# master2.net
KiCad netlist of a schematic drawn in EAGLE
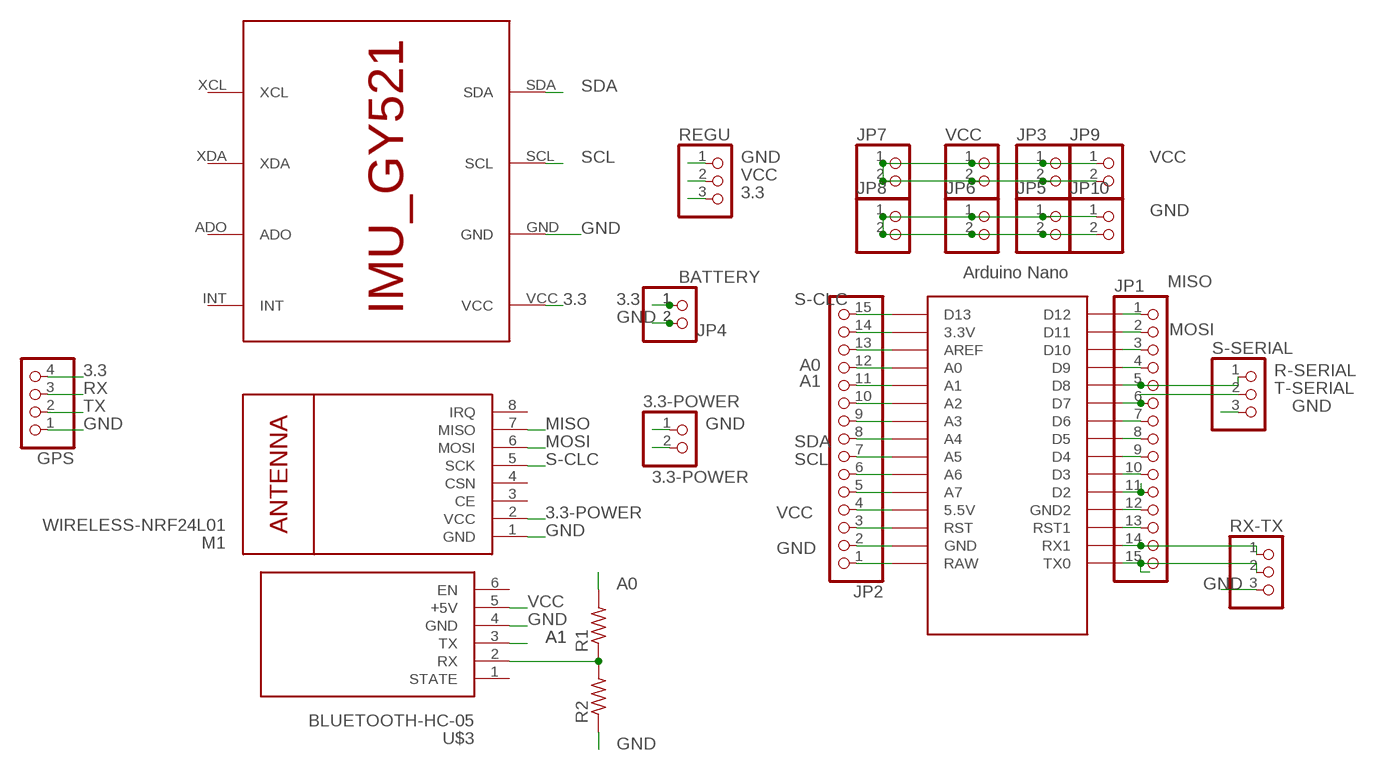
[diagram p0: schematic, sheet 1]

(export (version "E")
  (design (tool "Eeschema 10.0.6"))
  (components
    (comp (ref "3.3-POWER")
      (value "PINHD-2_DATA")
      (footprint "eagle-import:1X02_DATA")
      (libsource (lib "eagle-import") (part "PINHD-2_DATA"))
    )
    (comp (ref "BATTERY")
      (value "PINHD-2_DATA")
      (footprint "eagle-import:1X02_DATA")
      (libsource (lib "eagle-import") (part "PINHD-2_DATA"))
    )
    (comp (ref "GPS")
      (value "PINHD-1X4")
      (footprint "eagle-import:1X04")
      (libsource (lib "eagle-import") (part "PINHD-1X4"))
    )
    (comp (ref "JP1")
      (value "PINHD-1X15")
      (footprint "eagle-import:1X15")
      (libsource (lib "eagle-import") (part "PINHD-1X15"))
    )
    (comp (ref "JP2")
      (value "PINHD-1X15")
      (footprint "eagle-import:1X15")
      (libsource (lib "eagle-import") (part "PINHD-1X15"))
    )
    (comp (ref "JP3")
      (value "PINHD-1X2")
      (footprint "eagle-import:1X02")
      (libsource (lib "eagle-import") (part "PINHD-1X2"))
    )
    (comp (ref "JP4")
      (value "PINHD-2_DATA")
      (footprint "eagle-import:1X02_DATA")
      (libsource (lib "eagle-import") (part "PINHD-2_DATA"))
    )
    (comp (ref "JP5")
      (value "PINHD-1X2")
      (footprint "eagle-import:1X02")
      (libsource (lib "eagle-import") (part "PINHD-1X2"))
    )
    (comp (ref "JP6")
      (value "PINHD-1X2")
      (footprint "eagle-import:1X02")
      (libsource (lib "eagle-import") (part "PINHD-1X2"))
    )
    (comp (ref "JP7")
      (value "PINHD-1X2")
      (footprint "eagle-import:1X02")
      (libsource (lib "eagle-import") (part "PINHD-1X2"))
    )
    (comp (ref "JP8")
      (value "PINHD-1X2")
      (footprint "eagle-import:1X02")
      (libsource (lib "eagle-import") (part "PINHD-1X2"))
    )
    (comp (ref "JP9")
      (value "PINHD-1X2")
      (footprint "eagle-import:1X02")
      (libsource (lib "eagle-import") (part "PINHD-1X2"))
    )
    (comp (ref "JP10")
      (value "PINHD-1X2")
      (footprint "eagle-import:1X02")
      (libsource (lib "eagle-import") (part "PINHD-1X2"))
    )
    (comp (ref "M1")
      (value "WIRELESS-NRF24L01")
      (footprint "eagle-import:WIRELESS-NRF24L01")
      (libsource (lib "eagle-import") (part "WIRELESS-NRF24L01"))
    )
    (comp (ref "R1")
      (value "R-US_0204/2V")
      (footprint "eagle-import:0204V")
      (libsource (lib "eagle-import") (part "R-US_0204/2V"))
    )
    (comp (ref "R2")
      (value "R-US_0204/2V")
      (footprint "eagle-import:0204V")
      (libsource (lib "eagle-import") (part "R-US_0204/2V"))
    )
    (comp (ref "REGU")
      (value "PINHD-1X3")
      (footprint "eagle-import:1X03")
      (libsource (lib "eagle-import") (part "PINHD-1X3"))
    )
    (comp (ref "RX-TX")
      (value "PINHD-3_DATA")
      (footprint "eagle-import:1X03_DATA")
      (libsource (lib "eagle-import") (part "PINHD-3_DATA"))
    )
    (comp (ref "S-SERIAL")
      (value "PINHD-3_DATA")
      (footprint "eagle-import:1X03_DATA")
      (libsource (lib "eagle-import") (part "PINHD-3_DATA"))
    )
    (comp (ref "U$1")
      (value "ARDUINO_NANO")
      (footprint "eagle-import:NANO")
      (libsource (lib "eagle-import") (part "ARDUINO_NANO"))
    )
    (comp (ref "U$2")
      (value "IMU_ROBOCON")
      (footprint "eagle-import:IMU_GY521")
      (libsource (lib "eagle-import") (part "IMU_ROBOCON"))
    )
    (comp (ref "U$3")
      (value "BLUETOOTH-HC-05")
      (footprint "eagle-import:WIRELESS-BLUETOOTH-HC-05")
      (libsource (lib "eagle-import") (part "BLUETOOTH-HC-05"))
    )
    (comp (ref "VCC")
      (value "PINHD-1X2")
      (footprint "eagle-import:1X02")
      (libsource (lib "eagle-import") (part "PINHD-1X2"))
    )
  )
  (nets
    (net (code "1") (name "/3.3") (class "Default")
      (node (ref "BATTERY") (pin "1") (pinfunction "1_1") (pintype "passive"))
      (node (ref "GPS") (pin "4") (pinfunction "4_4") (pintype "passive"))
      (node (ref "JP4") (pin "1") (pinfunction "1_1") (pintype "passive"))
      (node (ref "REGU") (pin "3") (pinfunction "3_3") (pintype "passive"))
      (node (ref "U$2") (pin "VCC") (pinfunction "VCC_VCC") (pintype "bidirectional"))
    )
    (net (code "2") (name "/3.3-POWER") (class "Default")
      (node (ref "3.3-POWER") (pin "2") (pinfunction "2_2") (pintype "passive"))
      (node (ref "M1") (pin "2") (pinfunction "VCC_2") (pintype "power_in"))
    )
    (net (code "3") (name "/A0") (class "Default")
      (node (ref "JP2") (pin "12") (pinfunction "12_12") (pintype "passive"))
      (node (ref "R1") (pin "2") (pinfunction "2_2") (pintype "passive"))
      (node (ref "U$1") (pin "A0") (pinfunction "A0_A0") (pintype "bidirectional"))
    )
    (net (code "4") (name "/A1") (class "Default")
      (node (ref "JP2") (pin "11") (pinfunction "11_11") (pintype "passive"))
      (node (ref "U$1") (pin "A1") (pinfunction "A1_A1") (pintype "bidirectional"))
      (node (ref "U$3") (pin "3") (pinfunction "TX_3") (pintype "bidirectional"))
    )
    (net (code "5") (name "/GND") (class "Default")
      (node (ref "3.3-POWER") (pin "1") (pinfunction "1_1") (pintype "passive"))
      (node (ref "BATTERY") (pin "2") (pinfunction "2_2") (pintype "passive"))
      (node (ref "GPS") (pin "1") (pinfunction "1_1") (pintype "passive"))
      (node (ref "JP1") (pin "12") (pinfunction "12_12") (pintype "passive"))
      (node (ref "JP10") (pin "1") (pinfunction "1_1") (pintype "passive"))
      (node (ref "JP10") (pin "2") (pinfunction "2_2") (pintype "passive"))
      (node (ref "JP2") (pin "2") (pinfunction "2_2") (pintype "passive"))
      (node (ref "JP4") (pin "2") (pinfunction "2_2") (pintype "passive"))
      (node (ref "JP5") (pin "1") (pinfunction "1_1") (pintype "passive"))
      (node (ref "JP5") (pin "2") (pinfunction "2_2") (pintype "passive"))
      (node (ref "JP6") (pin "1") (pinfunction "1_1") (pintype "passive"))
      (node (ref "JP6") (pin "2") (pinfunction "2_2") (pintype "passive"))
      (node (ref "JP8") (pin "1") (pinfunction "1_1") (pintype "passive"))
      (node (ref "JP8") (pin "2") (pinfunction "2_2") (pintype "passive"))
      (node (ref "M1") (pin "1") (pinfunction "GND_1") (pintype "power_in"))
      (node (ref "R2") (pin "1") (pinfunction "1_1") (pintype "passive"))
      (node (ref "REGU") (pin "1") (pinfunction "1_1") (pintype "passive"))
      (node (ref "RX-TX") (pin "3") (pinfunction "3_3") (pintype "passive"))
      (node (ref "S-SERIAL") (pin "3") (pinfunction "3_3") (pintype "passive"))
      (node (ref "U$1") (pin "GND") (pinfunction "GND_GND") (pintype "bidirectional"))
      (node (ref "U$1") (pin "GND1") (pinfunction "GND2_GND1") (pintype "bidirectional"))
      (node (ref "U$2") (pin "GND") (pinfunction "GND_GND") (pintype "bidirectional"))
      (node (ref "U$3") (pin "4") (pinfunction "GND_4") (pintype "power_in"))
    )
    (net (code "6") (name "/MISO") (class "Default")
      (node (ref "JP1") (pin "1") (pinfunction "1_1") (pintype "passive"))
      (node (ref "M1") (pin "7") (pinfunction "MISO_7") (pintype "bidirectional"))
      (node (ref "U$1") (pin "D12") (pinfunction "D12_D12") (pintype "bidirectional"))
    )
    (net (code "7") (name "/MOSI") (class "Default")
      (node (ref "JP1") (pin "2") (pinfunction "2_2") (pintype "passive"))
      (node (ref "M1") (pin "6") (pinfunction "MOSI_6") (pintype "bidirectional"))
      (node (ref "U$1") (pin "D11") (pinfunction "D11_D11") (pintype "bidirectional"))
    )
    (net (code "8") (name "/R-SERIAL") (class "Default")
      (node (ref "JP1") (pin "5") (pinfunction "5_5") (pintype "passive"))
      (node (ref "S-SERIAL") (pin "1") (pinfunction "1_1") (pintype "passive"))
      (node (ref "U$1") (pin "D8") (pinfunction "D8_D8") (pintype "bidirectional"))
    )
    (net (code "9") (name "/RX") (class "Default")
      (node (ref "GPS") (pin "3") (pinfunction "3_3") (pintype "passive"))
    )
    (net (code "10") (name "/S-CLC") (class "Default")
      (node (ref "JP2") (pin "15") (pinfunction "15_15") (pintype "passive"))
      (node (ref "M1") (pin "5") (pinfunction "SCK_5") (pintype "bidirectional"))
      (node (ref "U$1") (pin "D13") (pinfunction "D13_D13") (pintype "bidirectional"))
    )
    (net (code "11") (name "/SCL") (class "Default")
      (node (ref "JP2") (pin "7") (pinfunction "7_7") (pintype "passive"))
      (node (ref "U$1") (pin "A5") (pinfunction "A5_A5") (pintype "bidirectional"))
      (node (ref "U$2") (pin "SCL") (pinfunction "SCL_SCL") (pintype "bidirectional"))
    )
    (net (code "12") (name "/SDA") (class "Default")
      (node (ref "JP2") (pin "8") (pinfunction "8_8") (pintype "passive"))
      (node (ref "U$1") (pin "A4") (pinfunction "A4_A4") (pintype "bidirectional"))
      (node (ref "U$2") (pin "SDA") (pinfunction "SDA_SDA") (pintype "bidirectional"))
    )
    (net (code "13") (name "/T-SERIAL") (class "Default")
      (node (ref "JP1") (pin "6") (pinfunction "6_6") (pintype "passive"))
      (node (ref "S-SERIAL") (pin "2") (pinfunction "2_2") (pintype "passive"))
      (node (ref "U$1") (pin "D7") (pinfunction "D7_D7") (pintype "bidirectional"))
    )
    (net (code "14") (name "/TX") (class "Default")
      (node (ref "GPS") (pin "2") (pinfunction "2_2") (pintype "passive"))
    )
    (net (code "15") (name "/VCC") (class "Default")
      (node (ref "JP2") (pin "4") (pinfunction "4_4") (pintype "passive"))
      (node (ref "JP3") (pin "1") (pinfunction "1_1") (pintype "passive"))
      (node (ref "JP3") (pin "2") (pinfunction "2_2") (pintype "passive"))
      (node (ref "JP7") (pin "1") (pinfunction "1_1") (pintype "passive"))
      (node (ref "JP7") (pin "2") (pinfunction "2_2") (pintype "passive"))
      (node (ref "JP9") (pin "1") (pinfunction "1_1") (pintype "passive"))
      (node (ref "JP9") (pin "2") (pinfunction "2_2") (pintype "passive"))
      (node (ref "REGU") (pin "2") (pinfunction "2_2") (pintype "passive"))
      (node (ref "U$1") (pin "5V") (pinfunction "5.5V_5V") (pintype "bidirectional"))
      (node (ref "U$3") (pin "5") (pinfunction "+5V_5") (pintype "power_in"))
      (node (ref "VCC") (pin "1") (pinfunction "1_1") (pintype "passive"))
      (node (ref "VCC") (pin "2") (pinfunction "2_2") (pintype "passive"))
    )
    (net (code "16") (name "Net-(JP1-Pad3)") (class "Default")
      (node (ref "JP1") (pin "3") (pinfunction "3_3") (pintype "passive"))
      (node (ref "U$1") (pin "D10") (pinfunction "D10_D10") (pintype "bidirectional"))
    )
    (net (code "17") (name "Net-(JP1-Pad4)") (class "Default")
      (node (ref "JP1") (pin "4") (pinfunction "4_4") (pintype "passive"))
      (node (ref "U$1") (pin "D9") (pinfunction "D9_D9") (pintype "bidirectional"))
    )
    (net (code "18") (name "Net-(JP1-Pad7)") (class "Default")
      (node (ref "JP1") (pin "7") (pinfunction "7_7") (pintype "passive"))
      (node (ref "U$1") (pin "D6") (pinfunction "D6_D6") (pintype "bidirectional"))
    )
    (net (code "19") (name "Net-(JP1-Pad8)") (class "Default")
      (node (ref "JP1") (pin "8") (pinfunction "8_8") (pintype "passive"))
      (node (ref "U$1") (pin "D5") (pinfunction "D5_D5") (pintype "bidirectional"))
    )
    (net (code "20") (name "Net-(JP1-Pad9)") (class "Default")
      (node (ref "JP1") (pin "9") (pinfunction "9_9") (pintype "passive"))
      (node (ref "U$1") (pin "D4") (pinfunction "D4_D4") (pintype "bidirectional"))
    )
    (net (code "21") (name "Net-(JP1-Pad10)") (class "Default")
      (node (ref "JP1") (pin "10") (pinfunction "10_10") (pintype "passive"))
      (node (ref "U$1") (pin "D3") (pinfunction "D3_D3") (pintype "bidirectional"))
    )
    (net (code "22") (name "Net-(JP1-Pad11)") (class "Default")
      (node (ref "JP1") (pin "11") (pinfunction "11_11") (pintype "passive"))
      (node (ref "U$1") (pin "D2") (pinfunction "D2_D2") (pintype "bidirectional"))
    )
    (net (code "23") (name "Net-(JP1-Pad13)") (class "Default")
      (node (ref "JP1") (pin "13") (pinfunction "13_13") (pintype "passive"))
      (node (ref "U$1") (pin "RST1") (pinfunction "RST1_RST1") (pintype "bidirectional"))
    )
    (net (code "24") (name "Net-(JP1-Pad14)") (class "Default")
      (node (ref "JP1") (pin "14") (pinfunction "14_14") (pintype "passive"))
      (node (ref "RX-TX") (pin "1") (pinfunction "1_1") (pintype "passive"))
      (node (ref "U$1") (pin "RX1") (pinfunction "RX1_RX1") (pintype "bidirectional"))
    )
    (net (code "25") (name "Net-(JP1-Pad15)") (class "Default")
      (node (ref "JP1") (pin "15") (pinfunction "15_15") (pintype "passive"))
      (node (ref "RX-TX") (pin "2") (pinfunction "2_2") (pintype "passive"))
      (node (ref "U$1") (pin "TX0") (pinfunction "TX0_TX0") (pintype "bidirectional"))
    )
    (net (code "26") (name "Net-(JP2-Pad1)") (class "Default")
      (node (ref "JP2") (pin "1") (pinfunction "1_1") (pintype "passive"))
      (node (ref "U$1") (pin "RAW") (pinfunction "RAW_RAW") (pintype "bidirectional"))
    )
    (net (code "27") (name "Net-(JP2-Pad3)") (class "Default")
      (node (ref "JP2") (pin "3") (pinfunction "3_3") (pintype "passive"))
      (node (ref "U$1") (pin "RST") (pinfunction "RST_RST") (pintype "bidirectional"))
    )
    (net (code "28") (name "Net-(JP2-Pad5)") (class "Default")
      (node (ref "JP2") (pin "5") (pinfunction "5_5") (pintype "passive"))
      (node (ref "U$1") (pin "A7") (pinfunction "A7_A7") (pintype "bidirectional"))
    )
    (net (code "29") (name "Net-(JP2-Pad6)") (class "Default")
      (node (ref "JP2") (pin "6") (pinfunction "6_6") (pintype "passive"))
      (node (ref "U$1") (pin "A6") (pinfunction "A6_A6") (pintype "bidirectional"))
    )
    (net (code "30") (name "Net-(JP2-Pad9)") (class "Default")
      (node (ref "JP2") (pin "9") (pinfunction "9_9") (pintype "passive"))
      (node (ref "U$1") (pin "A3") (pinfunction "A3_A3") (pintype "bidirectional"))
    )
    (net (code "31") (name "Net-(JP2-Pad10)") (class "Default")
      (node (ref "JP2") (pin "10") (pinfunction "10_10") (pintype "passive"))
      (node (ref "U$1") (pin "A2") (pinfunction "A2_A2") (pintype "bidirectional"))
    )
    (net (code "32") (name "Net-(JP2-Pad13)") (class "Default")
      (node (ref "JP2") (pin "13") (pinfunction "13_13") (pintype "passive"))
      (node (ref "U$1") (pin "AREF") (pinfunction "AREF_AREF") (pintype "bidirectional"))
    )
    (net (code "33") (name "Net-(JP2-Pad14)") (class "Default")
      (node (ref "JP2") (pin "14") (pinfunction "14_14") (pintype "passive"))
      (node (ref "U$1") (pin "3.3V") (pinfunction "3.3V_3.3V") (pintype "bidirectional"))
    )
    (net (code "34") (name "Net-(U$3-RX)") (class "Default")
      (node (ref "R1") (pin "1") (pinfunction "1_1") (pintype "passive"))
      (node (ref "R2") (pin "2") (pinfunction "2_2") (pintype "passive"))
      (node (ref "U$3") (pin "2") (pinfunction "RX_2") (pintype "bidirectional"))
    )
    (net (code "35") (name "unconnected-(M1-CE-Pad3)") (class "Default")
      (node (ref "M1") (pin "3") (pinfunction "CE_3") (pintype "bidirectional"))
    )
    (net (code "36") (name "unconnected-(M1-CSN-Pad4)") (class "Default")
      (node (ref "M1") (pin "4") (pinfunction "CSN_4") (pintype "bidirectional"))
    )
    (net (code "37") (name "unconnected-(M1-IRQ-Pad8)") (class "Default")
      (node (ref "M1") (pin "8") (pinfunction "IRQ_8") (pintype "bidirectional"))
    )
    (net (code "38") (name "unconnected-(U$2-PadADO)") (class "Default")
      (node (ref "U$2") (pin "ADO") (pinfunction "ADO_ADO") (pintype "bidirectional"))
    )
    (net (code "39") (name "unconnected-(U$2-PadINT)") (class "Default")
      (node (ref "U$2") (pin "INT") (pinfunction "INT_INT") (pintype "bidirectional"))
    )
    (net (code "40") (name "unconnected-(U$2-PadXCL)") (class "Default")
      (node (ref "U$2") (pin "XCL") (pinfunction "XCL_XCL") (pintype "bidirectional"))
    )
    (net (code "41") (name "unconnected-(U$2-PadXDA)") (class "Default")
      (node (ref "U$2") (pin "XDA") (pinfunction "XDA_XDA") (pintype "bidirectional"))
    )
    (net (code "42") (name "unconnected-(U$3-EN-Pad6)") (class "Default")
      (node (ref "U$3") (pin "6") (pinfunction "EN_6") (pintype "bidirectional"))
    )
    (net (code "43") (name "unconnected-(U$3-STATE-Pad1)") (class "Default")
      (node (ref "U$3") (pin "1") (pinfunction "STATE_1") (pintype "bidirectional"))
    )
  )
)
